# TUDSSL_condenar__Hardware_PCBs_PowerModu.net
KiCad netlist of a schematic drawn in Altium Designer
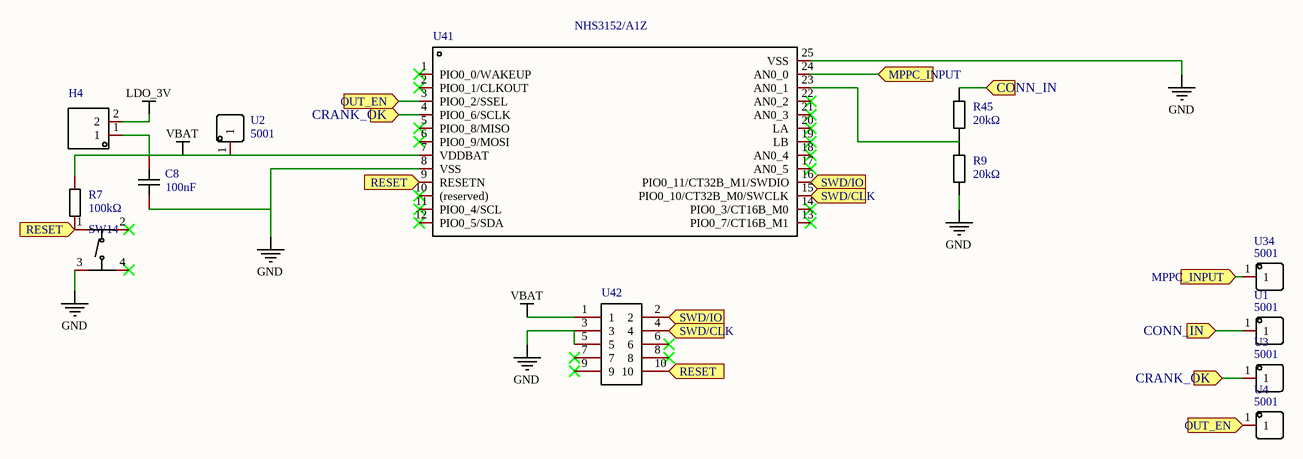
[diagram p0: TUDSSL_condenar__Hardware_PCBs_PowerModules_CrankModuleV2_SMART_TUD-EHC-CrankModule_3__2_MCU.schdoc]

(export (version "E")
  (design (tool "Eeschema 10.0.6"))
  (components
    (comp (ref "C8")
      (value "100nF")
      (fields
        (field (name "NAME") "100nF")
        (field (name "MANUFACTURER") "YAGEO")
        (field (name "MANUFACTURER PART") "CC0603KRX7R9BB104")
      )
      (libsource (lib "altium-import") (part "root_3_CC0603KRX7R9BB104_"))
    )
    (comp (ref "H4")
      (value "HDR-M_2.54_1x2P")
      (libsource (lib "altium-import") (part "root_2_HDR-M_2.54_1x2P_"))
    )
    (comp (ref "R7")
      (value "100kΩ")
      (fields
        (field (name "MANUFACTURER") "UNI-ROYAL(厚声)")
        (field (name "MANUFACTURER PART") "0603WAF1003T5E")
        (field (name "TOLERANCE") "±1%")
      )
      (libsource (lib "altium-import") (part "root_3_0603WAF1003T5E_"))
    )
    (comp (ref "R9")
      (value "20kΩ")
      (fields
        (field (name "NAME") "20kΩ")
        (field (name "MANUFACTURER") "UniOhm")
        (field (name "MANUFACTURER PART") "0603WAF2002T5E")
      )
      (libsource (lib "altium-import") (part "root_3_0603WAF2002T5E_"))
    )
    (comp (ref "R45")
      (value "20kΩ")
      (fields
        (field (name "NAME") "20kΩ")
        (field (name "MANUFACTURER") "UniOhm")
        (field (name "MANUFACTURER PART") "0603WAF2002T5E")
      )
      (libsource (lib "altium-import") (part "root_3_0603WAF2002T5E_"))
    )
    (comp (ref "SW14")
      (value "TS-1187A-B-A-B")
      (fields (field (name "MANUFACTURER") "XKB Connectivity(中国星坤)"))
      (libsource (lib "altium-import") (part "root_0_TS-1187A-B-A-B_"))
    )
    (comp (ref "U1")
      (value "5001")
      (fields (field (name "NAME") "5001") (field (name "MANUFACTURER") "Keystone"))
      (libsource (lib "altium-import") (part "root_0_5001_"))
    )
    (comp (ref "U2")
      (value "5001")
      (fields (field (name "NAME") "5001") (field (name "MANUFACTURER") "Keystone"))
      (libsource (lib "altium-import") (part "root_1_5001_"))
    )
    (comp (ref "U3")
      (value "5001")
      (fields (field (name "NAME") "5001") (field (name "MANUFACTURER") "Keystone"))
      (libsource (lib "altium-import") (part "root_0_5001_"))
    )
    (comp (ref "U4")
      (value "5001")
      (fields (field (name "NAME") "5001") (field (name "MANUFACTURER") "Keystone"))
      (libsource (lib "altium-import") (part "root_0_5001_"))
    )
    (comp (ref "U34")
      (value "5001")
      (fields (field (name "NAME") "5001") (field (name "MANUFACTURER") "Keystone"))
      (libsource (lib "altium-import") (part "root_0_5001_"))
    )
    (comp (ref "U41")
      (value "NHS3152/A1Z")
      (fields (field (name "MANUFACTURER") "NXP(恩智浦)") (field (name "MANUFACTURER PART") "NHS3152/A1Z"))
      (libsource (lib "altium-import") (part "root_0_NHS3152/A1Z_"))
    )
    (comp (ref "U42")
      (value "20021121-00010T4LF")
      (fields (field (name "MANUFACTURER") "Amphenol"))
      (libsource (lib "altium-import") (part "root_3_20021121-00010T4LF_"))
    )
  )
  (nets
    (net (code "1") (name "/CONN_IN") (class "Default")
      (node (ref "R45") (pin "1") (pinfunction "1_1") (pintype "passive"))
      (node (ref "U1") (pin "1") (pinfunction "1_1") (pintype "passive"))
    )
    (net (code "2") (name "/CRANK_OK") (class "Default")
      (node (ref "U3") (pin "1") (pinfunction "1_1") (pintype "passive"))
      (node (ref "U41") (pin "4") (pinfunction "PIO0_6/SCLK_4") (pintype "passive"))
    )
    (net (code "3") (name "/MPPC_INPUT") (class "Default")
      (node (ref "U34") (pin "1") (pinfunction "1_1") (pintype "passive"))
      (node (ref "U41") (pin "24") (pinfunction "AN0_0_24") (pintype "passive"))
    )
    (net (code "4") (name "/OUT_EN") (class "Default")
      (node (ref "U4") (pin "1") (pinfunction "1_1") (pintype "passive"))
      (node (ref "U41") (pin "3") (pinfunction "PIO0_2/SSEL_3") (pintype "passive"))
    )
    (net (code "5") (name "/RESET") (class "Default")
      (node (ref "R7") (pin "2") (pinfunction "2_2") (pintype "passive"))
      (node (ref "SW14") (pin "1") (pinfunction "A_1") (pintype "passive"))
      (node (ref "U41") (pin "9") (pinfunction "RESETN_9") (pintype "passive"))
      (node (ref "U42") (pin "10") (pinfunction "10_10") (pintype "passive"))
    )
    (net (code "6") (name "/SWD{slash}CLK") (class "Default")
      (node (ref "U41") (pin "15") (pinfunction "PIO0_10/CT32B_M0/SWCLK_15") (pintype "passive"))
      (node (ref "U42") (pin "4") (pinfunction "4_4") (pintype "passive"))
    )
    (net (code "7") (name "/SWD{slash}IO") (class "Default")
      (node (ref "U41") (pin "16") (pinfunction "PIO0_11/CT32B_M1/SWDIO_16") (pintype "passive"))
      (node (ref "U42") (pin "2") (pinfunction "2_2") (pintype "passive"))
    )
    (net (code "8") (name "GND") (class "Default")
      (node (ref "C8") (pin "2") (pinfunction "2_2") (pintype "passive"))
      (node (ref "R9") (pin "2") (pinfunction "2_2") (pintype "passive"))
      (node (ref "SW14") (pin "3") (pinfunction "C_3") (pintype "passive"))
      (node (ref "U41") (pin "25") (pinfunction "VSS_25") (pintype "passive"))
      (node (ref "U41") (pin "8") (pinfunction "VSS_8") (pintype "passive"))
      (node (ref "U42") (pin "3") (pinfunction "3_3") (pintype "passive"))
      (node (ref "U42") (pin "5") (pinfunction "5_5") (pintype "passive"))
    )
    (net (code "9") (name "LDO_3V") (class "Default")
      (node (ref "H4") (pin "2") (pinfunction "2_2") (pintype "passive"))
    )
    (net (code "10") (name "Net-(U41-AN0_1)") (class "Default")
      (node (ref "R45") (pin "2") (pinfunction "2_2") (pintype "passive"))
      (node (ref "R9") (pin "1") (pinfunction "1_1") (pintype "passive"))
      (node (ref "U41") (pin "23") (pinfunction "AN0_1_23") (pintype "passive"))
    )
    (net (code "11") (name "VBAT") (class "Default")
      (node (ref "C8") (pin "1") (pinfunction "1_1") (pintype "passive"))
      (node (ref "H4") (pin "1") (pinfunction "1_1") (pintype "passive"))
      (node (ref "R7") (pin "1") (pinfunction "1_1") (pintype "passive"))
      (node (ref "U2") (pin "1") (pinfunction "1_1") (pintype "passive"))
      (node (ref "U41") (pin "7") (pinfunction "VDDBAT_7") (pintype "passive"))
      (node (ref "U42") (pin "1") (pinfunction "1_1") (pintype "passive"))
    )
    (net (code "12") (name "unconnected-(SW14-B-Pad2)") (class "Default")
      (node (ref "SW14") (pin "2") (pinfunction "B_2") (pintype "passive+no_connect"))
    )
    (net (code "13") (name "unconnected-(SW14-D-Pad4)") (class "Default")
      (node (ref "SW14") (pin "4") (pinfunction "D_4") (pintype "passive+no_connect"))
    )
    (net (code "14") (name "unconnected-(U41-(reserved)-Pad10)") (class "Default")
      (node (ref "U41") (pin "10") (pinfunction "(reserved)_10") (pintype "passive+no_connect"))
    )
    (net (code "15") (name "unconnected-(U41-AN0_2-Pad22)") (class "Default")
      (node (ref "U41") (pin "22") (pinfunction "AN0_2_22") (pintype "passive+no_connect"))
    )
    (net (code "16") (name "unconnected-(U41-AN0_3-Pad21)") (class "Default")
      (node (ref "U41") (pin "21") (pinfunction "AN0_3_21") (pintype "passive+no_connect"))
    )
    (net (code "17") (name "unconnected-(U41-AN0_4-Pad18)") (class "Default")
      (node (ref "U41") (pin "18") (pinfunction "AN0_4_18") (pintype "passive+no_connect"))
    )
    (net (code "18") (name "unconnected-(U41-AN0_5-Pad17)") (class "Default")
      (node (ref "U41") (pin "17") (pinfunction "AN0_5_17") (pintype "passive+no_connect"))
    )
    (net (code "19") (name "unconnected-(U41-LA-Pad20)") (class "Default")
      (node (ref "U41") (pin "20") (pinfunction "LA_20") (pintype "passive+no_connect"))
    )
    (net (code "20") (name "unconnected-(U41-LB-Pad19)") (class "Default")
      (node (ref "U41") (pin "19") (pinfunction "LB_19") (pintype "passive+no_connect"))
    )
    (net (code "21") (name "unconnected-(U41-PIO0_0{slash}WAKEUP-Pad1)") (class "Default")
      (node (ref "U41") (pin "1") (pinfunction "PIO0_0/WAKEUP_1") (pintype "passive+no_connect"))
    )
    (net (code "22") (name "unconnected-(U41-PIO0_1{slash}CLKOUT-Pad2)") (class "Default")
      (node (ref "U41") (pin "2") (pinfunction "PIO0_1/CLKOUT_2") (pintype "passive+no_connect"))
    )
    (net (code "23") (name "unconnected-(U41-PIO0_3{slash}CT16B_M0-Pad14)") (class "Default")
      (node (ref "U41") (pin "14") (pinfunction "PIO0_3/CT16B_M0_14") (pintype "passive+no_connect"))
    )
    (net (code "24") (name "unconnected-(U41-PIO0_4{slash}SCL-Pad11)") (class "Default")
      (node (ref "U41") (pin "11") (pinfunction "PIO0_4/SCL_11") (pintype "passive+no_connect"))
    )
    (net (code "25") (name "unconnected-(U41-PIO0_5{slash}SDA-Pad12)") (class "Default")
      (node (ref "U41") (pin "12") (pinfunction "PIO0_5/SDA_12") (pintype "passive+no_connect"))
    )
    (net (code "26") (name "unconnected-(U41-PIO0_7{slash}CT16B_M1-Pad13)") (class "Default")
      (node (ref "U41") (pin "13") (pinfunction "PIO0_7/CT16B_M1_13") (pintype "passive+no_connect"))
    )
    (net (code "27") (name "unconnected-(U41-PIO0_8{slash}MISO-Pad5)") (class "Default")
      (node (ref "U41") (pin "5") (pinfunction "PIO0_8/MISO_5") (pintype "passive+no_connect"))
    )
    (net (code "28") (name "unconnected-(U41-PIO0_9{slash}MOSI-Pad6)") (class "Default")
      (node (ref "U41") (pin "6") (pinfunction "PIO0_9/MOSI_6") (pintype "passive+no_connect"))
    )
    (net (code "29") (name "unconnected-(U42-Pad6)") (class "Default")
      (node (ref "U42") (pin "6") (pinfunction "6_6") (pintype "passive+no_connect"))
    )
    (net (code "30") (name "unconnected-(U42-Pad7)") (class "Default")
      (node (ref "U42") (pin "7") (pinfunction "7_7") (pintype "passive+no_connect"))
    )
    (net (code "31") (name "unconnected-(U42-Pad8)") (class "Default")
      (node (ref "U42") (pin "8") (pinfunction "8_8") (pintype "passive+no_connect"))
    )
    (net (code "32") (name "unconnected-(U42-Pad9)") (class "Default")
      (node (ref "U42") (pin "9") (pinfunction "9_9") (pintype "passive+no_connect"))
    )
  )
)
